# charging.net
KiCad netlist of a schematic drawn in EAGLE
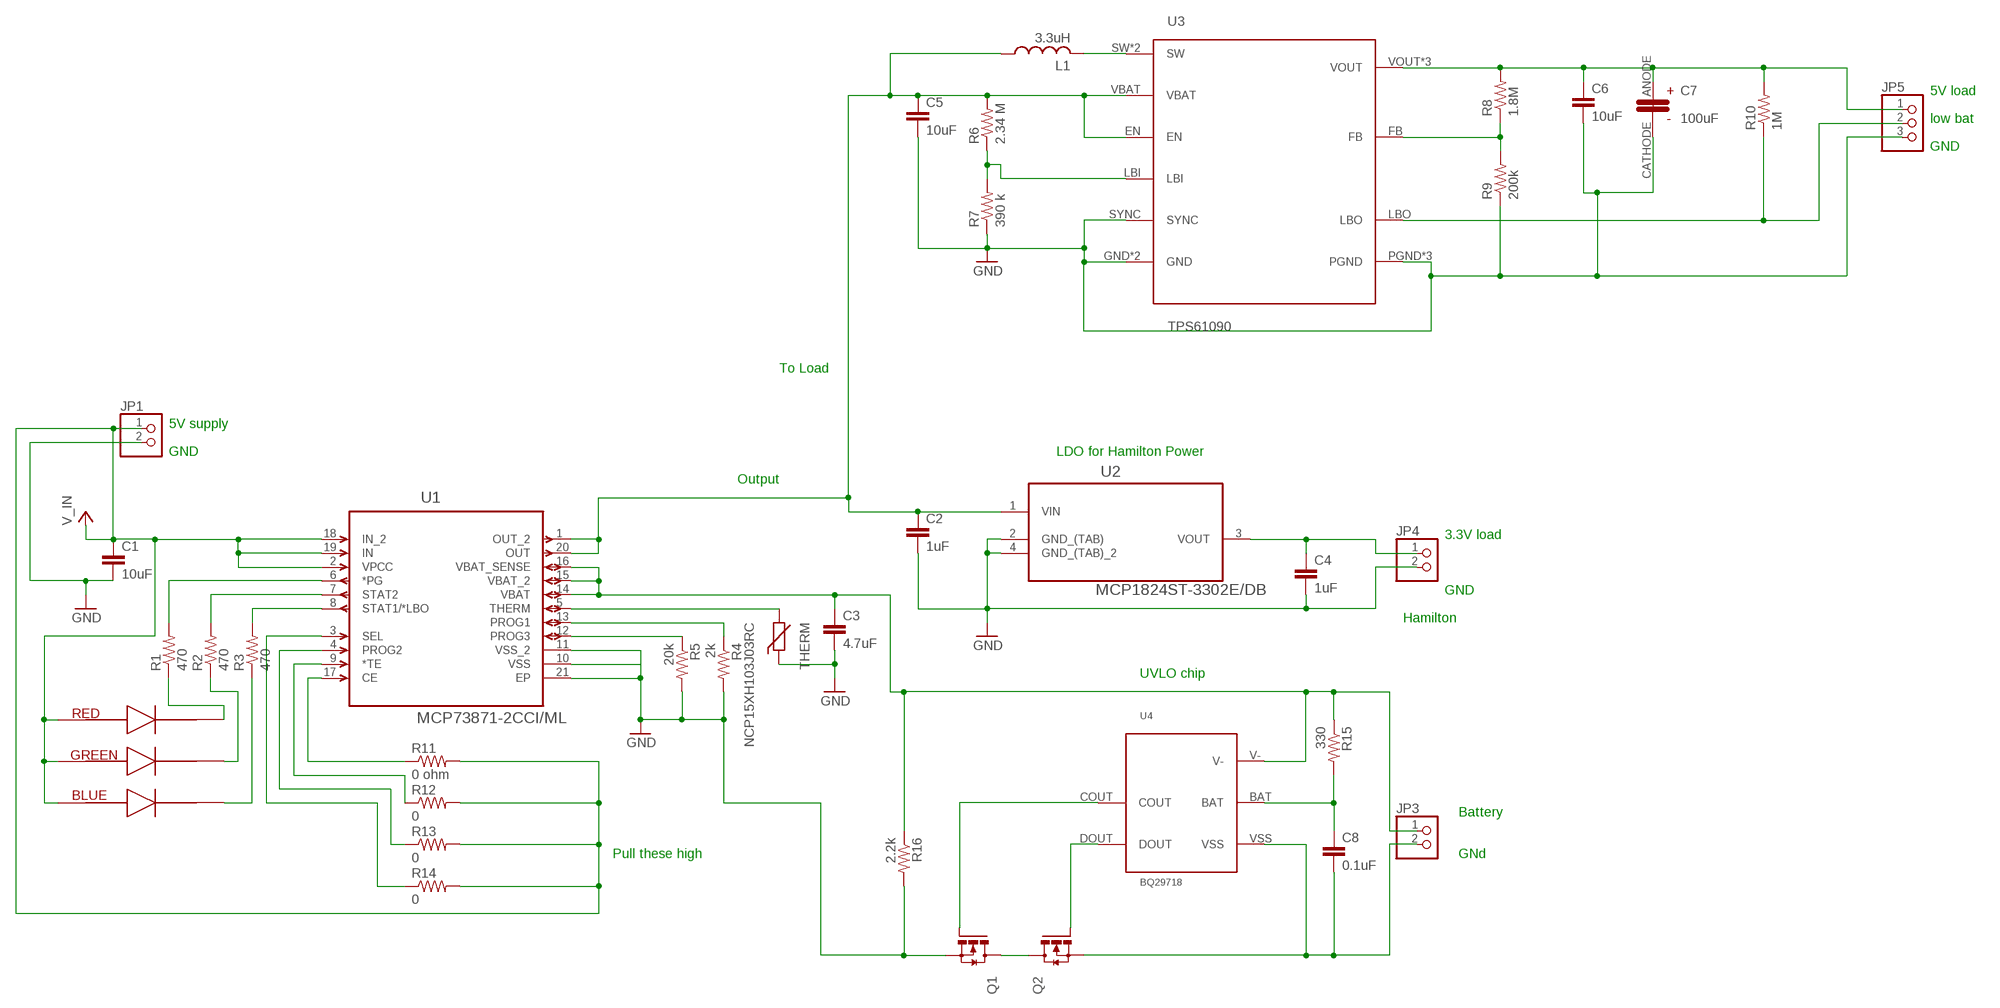
[diagram p0: schematic, sheet 1]

(export (version "E")
  (design (tool "Eeschema 10.0.6"))
  (components
    (comp (ref "C1")
      (value "10uF")
      (footprint "eagle-import:C0805")
      (libsource (lib "eagle-import") (part "C-EUC0805"))
    )
    (comp (ref "C2")
      (value "1uF")
      (footprint "eagle-import:C0603K")
      (libsource (lib "eagle-import") (part "C-EUC0603K"))
    )
    (comp (ref "C3")
      (value "4.7uF")
      (footprint "eagle-import:C0805")
      (libsource (lib "eagle-import") (part "C-EUC0805"))
    )
    (comp (ref "C4")
      (value "1uF")
      (footprint "eagle-import:C0603K")
      (libsource (lib "eagle-import") (part "C-EUC0603K"))
    )
    (comp (ref "C5")
      (value "10uF")
      (footprint "eagle-import:C0603K")
      (libsource (lib "eagle-import") (part "C-EUC0603K"))
    )
    (comp (ref "C6")
      (value "10uF")
      (footprint "eagle-import:C0603K")
      (libsource (lib "eagle-import") (part "C-EUC0603K"))
    )
    (comp (ref "C7")
      (value "100uF")
      (footprint "eagle-import:6032")
      (libsource (lib "eagle-import") (part "T491C686K010AT"))
    )
    (comp (ref "C8")
      (value "0.1uF")
      (footprint "eagle-import:C0805")
      (libsource (lib "eagle-import") (part "C-EUC0805"))
    )
    (comp (ref "JP1")
      (value "PINHD-1X2")
      (footprint "eagle-import:1X02")
      (libsource (lib "eagle-import") (part "PINHD-1X2"))
    )
    (comp (ref "JP3")
      (value "PINHD-1X2")
      (footprint "eagle-import:1X02")
      (libsource (lib "eagle-import") (part "PINHD-1X2"))
    )
    (comp (ref "JP4")
      (value "PINHD-1X2")
      (footprint "eagle-import:1X02")
      (libsource (lib "eagle-import") (part "PINHD-1X2"))
    )
    (comp (ref "JP5")
      (value "PINHD-1X3")
      (footprint "eagle-import:1X03")
      (libsource (lib "eagle-import") (part "PINHD-1X3"))
    )
    (comp (ref "L1")
      (value "3.3uH")
      (footprint "eagle-import:2-SMD")
      (libsource (lib "eagle-import") (part "L-US"))
    )
    (comp (ref "Q1")
      (value "CSD16301Q2")
      (footprint "eagle-import:6-SMD")
      (libsource (lib "eagle-import") (part "CSD16301Q2"))
    )
    (comp (ref "Q2")
      (value "CSD16301Q2")
      (footprint "eagle-import:6-SMD")
      (libsource (lib "eagle-import") (part "CSD16301Q2"))
    )
    (comp (ref "R1")
      (value "470")
      (footprint "eagle-import:R0805")
      (libsource (lib "eagle-import") (part "R-US_R0805"))
    )
    (comp (ref "R2")
      (value "470")
      (footprint "eagle-import:R0805")
      (libsource (lib "eagle-import") (part "R-US_R0805"))
    )
    (comp (ref "R3")
      (value "470")
      (footprint "eagle-import:R0805")
      (libsource (lib "eagle-import") (part "R-US_R0805"))
    )
    (comp (ref "R4")
      (value "2k")
      (footprint "eagle-import:R0805")
      (libsource (lib "eagle-import") (part "R-US_R0805"))
    )
    (comp (ref "R5")
      (value "20k")
      (footprint "eagle-import:R0805")
      (libsource (lib "eagle-import") (part "R-US_R0805"))
    )
    (comp (ref "R6")
      (value "2.34 M")
      (footprint "eagle-import:R0603")
      (libsource (lib "eagle-import") (part "R-US_R0603"))
    )
    (comp (ref "R7")
      (value "390 k")
      (footprint "eagle-import:R0603")
      (libsource (lib "eagle-import") (part "R-US_R0603"))
    )
    (comp (ref "R8")
      (value "1.8M")
      (footprint "eagle-import:R0603")
      (libsource (lib "eagle-import") (part "R-US_R0603"))
    )
    (comp (ref "R9")
      (value "200k")
      (footprint "eagle-import:R0603")
      (libsource (lib "eagle-import") (part "R-US_R0603"))
    )
    (comp (ref "R10")
      (value "1M")
      (footprint "eagle-import:R0603")
      (libsource (lib "eagle-import") (part "R-US_R0603"))
    )
    (comp (ref "R11")
      (value "0 ohm")
      (footprint "eagle-import:R0603")
      (libsource (lib "eagle-import") (part "R-US_R0603"))
    )
    (comp (ref "R12")
      (value "0")
      (footprint "eagle-import:R0603")
      (libsource (lib "eagle-import") (part "R-US_R0603"))
    )
    (comp (ref "R13")
      (value "0")
      (footprint "eagle-import:R0603")
      (libsource (lib "eagle-import") (part "R-US_R0603"))
    )
    (comp (ref "R14")
      (value "0")
      (footprint "eagle-import:R0603")
      (libsource (lib "eagle-import") (part "R-US_R0603"))
    )
    (comp (ref "R15")
      (value "330")
      (footprint "eagle-import:R0805")
      (libsource (lib "eagle-import") (part "R-US_R0805"))
    )
    (comp (ref "R16")
      (value "2.2k")
      (footprint "eagle-import:R0805")
      (libsource (lib "eagle-import") (part "R-US_R0805"))
    )
    (comp (ref "THERM")
      (value "NCP15XH103J03RC")
      (footprint "eagle-import:CT_CN0402")
      (libsource (lib "eagle-import") (part "NCP15XH103J03RC"))
    )
    (comp (ref "U$1")
      (value "CLP6C-FKB")
      (footprint "eagle-import:CREE_PLCC6_3-IN-1_SMD_LED_CLP6C-FKB")
      (libsource (lib "eagle-import") (part "CLP6C-FKB"))
    )
    (comp (ref "U1")
      (value "MCP73871-2CCI/ML")
      (footprint "eagle-import:QFN50P400X400X100-21N")
      (libsource (lib "eagle-import") (part "MCP73871-2CCI/ML"))
    )
    (comp (ref "U2")
      (value "MCP1824ST-3302E/DB")
      (footprint "eagle-import:SOT230P700X180-4N")
      (libsource (lib "eagle-import") (part "MCP1824ST-3302E/DB"))
    )
    (comp (ref "U3")
      (value "TPS61090")
      (footprint "eagle-import:QFN-16")
      (libsource (lib "eagle-import") (part "TPS61090"))
    )
    (comp (ref "U4")
      (value "BQ29718")
      (footprint "eagle-import:6-WFDFN")
      (libsource (lib "eagle-import") (part "BQ29718"))
    )
  )
  (nets
    (net (code "1") (name "GND") (class "Default")
      (node (ref "C1") (pin "2") (pinfunction "2_2") (pintype "passive"))
      (node (ref "C2") (pin "2") (pinfunction "2_2") (pintype "passive"))
      (node (ref "C3") (pin "2") (pinfunction "2_2") (pintype "passive"))
      (node (ref "C4") (pin "2") (pinfunction "2_2") (pintype "passive"))
      (node (ref "C5") (pin "2") (pinfunction "2_2") (pintype "passive"))
      (node (ref "C6") (pin "2") (pinfunction "2_2") (pintype "passive"))
      (node (ref "C7") (pin "CATHODE") (pinfunction "CATHODE_CATHODE") (pintype "bidirectional"))
      (node (ref "JP1") (pin "2") (pinfunction "2_2") (pintype "passive"))
      (node (ref "JP4") (pin "2") (pinfunction "2_2") (pintype "passive"))
      (node (ref "JP5") (pin "3") (pinfunction "3_3") (pintype "passive"))
      (node (ref "Q1") (pin "S_1") (pinfunction "S_S_1") (pintype "passive"))
      (node (ref "Q1") (pin "S_2") (pinfunction "S_S_2") (pintype "passive"))
      (node (ref "R16") (pin "2") (pinfunction "2_2") (pintype "passive"))
      (node (ref "R4") (pin "2") (pinfunction "2_2") (pintype "passive"))
      (node (ref "R5") (pin "2") (pinfunction "2_2") (pintype "passive"))
      (node (ref "R7") (pin "1") (pinfunction "1_1") (pintype "passive"))
      (node (ref "R9") (pin "1") (pinfunction "1_1") (pintype "passive"))
      (node (ref "THERM") (pin "1") (pinfunction "1_1") (pintype "passive"))
      (node (ref "U1") (pin "10") (pinfunction "VSS_10") (pintype "power_in"))
      (node (ref "U1") (pin "11") (pinfunction "VSS_2_11") (pintype "power_in"))
      (node (ref "U1") (pin "21") (pinfunction "EP_21") (pintype "passive"))
      (node (ref "U2") (pin "2") (pinfunction "GND_(TAB)_2") (pintype "passive"))
      (node (ref "U2") (pin "4") (pinfunction "GND_(TAB)_2_4") (pintype "passive"))
      (node (ref "U3") (pin "GND") (pinfunction "GND_GND") (pintype "bidirectional"))
      (node (ref "U3") (pin "P$17") (pinfunction "GND_P$17") (pintype "bidirectional"))
      (node (ref "U3") (pin "PGND") (pinfunction "PGND_PGND") (pintype "bidirectional"))
      (node (ref "U3") (pin "PGND_2") (pinfunction "PGND_PGND_2") (pintype "bidirectional"))
      (node (ref "U3") (pin "PGND_3") (pinfunction "PGND_PGND_3") (pintype "bidirectional"))
      (node (ref "U3") (pin "SYNC") (pinfunction "SYNC_SYNC") (pintype "bidirectional"))
    )
    (net (code "2") (name "Net-(C6-Pad1)") (class "Default")
      (node (ref "C6") (pin "1") (pinfunction "1_1") (pintype "passive"))
      (node (ref "C7") (pin "ANODE") (pinfunction "ANODE_ANODE") (pintype "bidirectional"))
      (node (ref "JP5") (pin "1") (pinfunction "1_1") (pintype "passive"))
      (node (ref "R10") (pin "2") (pinfunction "2_2") (pintype "passive"))
      (node (ref "R8") (pin "2") (pinfunction "2_2") (pintype "passive"))
      (node (ref "U3") (pin "VOUT") (pinfunction "VOUT_VOUT") (pintype "bidirectional"))
      (node (ref "U3") (pin "VOUT_2") (pinfunction "VOUT_VOUT_2") (pintype "bidirectional"))
      (node (ref "U3") (pin "VOUT_3") (pinfunction "VOUT_VOUT_3") (pintype "bidirectional"))
    )
    (net (code "3") (name "Net-(C8-Pad1)") (class "Default")
      (node (ref "C8") (pin "1") (pinfunction "1_1") (pintype "passive"))
      (node (ref "R15") (pin "2") (pinfunction "2_2") (pintype "passive"))
      (node (ref "U4") (pin "BAT") (pinfunction "BAT_BAT") (pintype "bidirectional"))
    )
    (net (code "4") (name "Net-(C8-Pad2)") (class "Default")
      (node (ref "C8") (pin "2") (pinfunction "2_2") (pintype "passive"))
      (node (ref "JP3") (pin "2") (pinfunction "2_2") (pintype "passive"))
      (node (ref "Q2") (pin "S_1") (pinfunction "S_S_1") (pintype "passive"))
      (node (ref "Q2") (pin "S_2") (pinfunction "S_S_2") (pintype "passive"))
      (node (ref "U4") (pin "VSS") (pinfunction "VSS_VSS") (pintype "bidirectional"))
    )
    (net (code "5") (name "Net-(JP5-Pad2)") (class "Default")
      (node (ref "JP5") (pin "2") (pinfunction "2_2") (pintype "passive"))
      (node (ref "R10") (pin "1") (pinfunction "1_1") (pintype "passive"))
      (node (ref "U3") (pin "LBO") (pinfunction "LBO_LBO") (pintype "bidirectional"))
    )
    (net (code "6") (name "Net-(L1-1)") (class "Default")
      (node (ref "C2") (pin "1") (pinfunction "1_1") (pintype "passive"))
      (node (ref "C5") (pin "1") (pinfunction "1_1") (pintype "passive"))
      (node (ref "L1") (pin "P$1") (pinfunction "1_P$1") (pintype "passive"))
      (node (ref "R6") (pin "2") (pinfunction "2_2") (pintype "passive"))
      (node (ref "U1") (pin "1") (pinfunction "OUT_2_1") (pintype "output"))
      (node (ref "U1") (pin "20") (pinfunction "OUT_20") (pintype "output"))
      (node (ref "U2") (pin "1") (pinfunction "VIN_1") (pintype "input"))
      (node (ref "U3") (pin "EN") (pinfunction "EN_EN") (pintype "bidirectional"))
      (node (ref "U3") (pin "VBAT") (pinfunction "VBAT_VBAT") (pintype "bidirectional"))
    )
    (net (code "7") (name "Net-(L1-2)") (class "Default")
      (node (ref "L1") (pin "P$2") (pinfunction "2_P$2") (pintype "passive"))
      (node (ref "U3") (pin "SW") (pinfunction "SW_SW") (pintype "bidirectional"))
      (node (ref "U3") (pin "SW_2") (pinfunction "SW_SW_2") (pintype "bidirectional"))
    )
    (net (code "8") (name "Net-(Q1-D-PadD_1)") (class "Default")
      (node (ref "Q1") (pin "D_1") (pinfunction "D_D_1") (pintype "passive"))
      (node (ref "Q1") (pin "D_2") (pinfunction "D_D_2") (pintype "passive"))
      (node (ref "Q1") (pin "D_3") (pinfunction "D_D_3") (pintype "passive"))
      (node (ref "Q1") (pin "D_4") (pinfunction "D_D_4") (pintype "passive"))
      (node (ref "Q1") (pin "D_5") (pinfunction "D_D_5") (pintype "passive"))
      (node (ref "Q2") (pin "D_1") (pinfunction "D_D_1") (pintype "passive"))
      (node (ref "Q2") (pin "D_2") (pinfunction "D_D_2") (pintype "passive"))
      (node (ref "Q2") (pin "D_3") (pinfunction "D_D_3") (pintype "passive"))
      (node (ref "Q2") (pin "D_4") (pinfunction "D_D_4") (pintype "passive"))
      (node (ref "Q2") (pin "D_5") (pinfunction "D_D_5") (pintype "passive"))
    )
    (net (code "9") (name "Net-(Q1-PadG)") (class "Default")
      (node (ref "Q1") (pin "G") (pinfunction "G_G") (pintype "passive"))
      (node (ref "U4") (pin "COUT") (pinfunction "COUT_COUT") (pintype "bidirectional"))
    )
    (net (code "10") (name "Net-(Q2-PadG)") (class "Default")
      (node (ref "Q2") (pin "G") (pinfunction "G_G") (pintype "passive"))
      (node (ref "U4") (pin "DOUT") (pinfunction "DOUT_DOUT") (pintype "bidirectional"))
    )
    (net (code "11") (name "Net-(R1-Pad1)") (class "Default")
      (node (ref "R1") (pin "1") (pinfunction "1_1") (pintype "passive"))
      (node (ref "U$1") (pin "RED_CATHODE") (pinfunction "RED_CATHODE_RED_CATHODE") (pintype "bidirectional"))
    )
    (net (code "12") (name "Net-(R2-Pad1)") (class "Default")
      (node (ref "R2") (pin "1") (pinfunction "1_1") (pintype "passive"))
      (node (ref "U$1") (pin "GREEN_CATHODE") (pinfunction "GREEN_CATHODE_GREEN_CATHODE") (pintype "bidirectional"))
    )
    (net (code "13") (name "Net-(R3-Pad1)") (class "Default")
      (node (ref "R3") (pin "1") (pinfunction "1_1") (pintype "passive"))
      (node (ref "U$1") (pin "BLUE_CATHODE") (pinfunction "BLUE_CATHODE_BLUE_CATHODE") (pintype "bidirectional"))
    )
    (net (code "14") (name "Net-(R6-Pad1)") (class "Default")
      (node (ref "R6") (pin "1") (pinfunction "1_1") (pintype "passive"))
      (node (ref "R7") (pin "2") (pinfunction "2_2") (pintype "passive"))
      (node (ref "U3") (pin "LBI") (pinfunction "LBI_LBI") (pintype "bidirectional"))
    )
    (net (code "15") (name "Net-(R8-Pad1)") (class "Default")
      (node (ref "R8") (pin "1") (pinfunction "1_1") (pintype "passive"))
      (node (ref "R9") (pin "2") (pinfunction "2_2") (pintype "passive"))
      (node (ref "U3") (pin "FB") (pinfunction "FB_FB") (pintype "bidirectional"))
    )
    (net (code "16") (name "Net-(U1-*PG)") (class "Default")
      (node (ref "R1") (pin "2") (pinfunction "2_2") (pintype "passive"))
      (node (ref "U1") (pin "6") (pinfunction "*PG_6") (pintype "output"))
    )
    (net (code "17") (name "Net-(U1-*TE)") (class "Default")
      (node (ref "R12") (pin "1") (pinfunction "1_1") (pintype "passive"))
      (node (ref "U1") (pin "9") (pinfunction "*TE_9") (pintype "input"))
    )
    (net (code "18") (name "Net-(U1-CE)") (class "Default")
      (node (ref "R11") (pin "1") (pinfunction "1_1") (pintype "passive"))
      (node (ref "U1") (pin "17") (pinfunction "CE_17") (pintype "input"))
    )
    (net (code "19") (name "Net-(U1-PROG1)") (class "Default")
      (node (ref "R4") (pin "1") (pinfunction "1_1") (pintype "passive"))
      (node (ref "U1") (pin "13") (pinfunction "PROG1_13") (pintype "bidirectional"))
    )
    (net (code "20") (name "Net-(U1-PROG2)") (class "Default")
      (node (ref "R13") (pin "1") (pinfunction "1_1") (pintype "passive"))
      (node (ref "U1") (pin "4") (pinfunction "PROG2_4") (pintype "input"))
    )
    (net (code "21") (name "Net-(U1-PROG3)") (class "Default")
      (node (ref "R5") (pin "1") (pinfunction "1_1") (pintype "passive"))
      (node (ref "U1") (pin "12") (pinfunction "PROG3_12") (pintype "bidirectional"))
    )
    (net (code "22") (name "Net-(U1-SEL)") (class "Default")
      (node (ref "R14") (pin "1") (pinfunction "1_1") (pintype "passive"))
      (node (ref "U1") (pin "3") (pinfunction "SEL_3") (pintype "input"))
    )
    (net (code "23") (name "Net-(U1-STAT1{slash}*LBO)") (class "Default")
      (node (ref "R3") (pin "2") (pinfunction "2_2") (pintype "passive"))
      (node (ref "U1") (pin "8") (pinfunction "STAT1/*LBO_8") (pintype "output"))
    )
    (net (code "24") (name "Net-(U1-STAT2)") (class "Default")
      (node (ref "R2") (pin "2") (pinfunction "2_2") (pintype "passive"))
      (node (ref "U1") (pin "7") (pinfunction "STAT2_7") (pintype "output"))
    )
    (net (code "25") (name "Net-(U1-THERM)") (class "Default")
      (node (ref "THERM") (pin "2") (pinfunction "2_2") (pintype "passive"))
      (node (ref "U1") (pin "5") (pinfunction "THERM_5") (pintype "bidirectional"))
    )
    (net (code "26") (name "Net-(U1-VBAT)") (class "Default")
      (node (ref "C3") (pin "1") (pinfunction "1_1") (pintype "passive"))
      (node (ref "JP3") (pin "1") (pinfunction "1_1") (pintype "passive"))
      (node (ref "R15") (pin "1") (pinfunction "1_1") (pintype "passive"))
      (node (ref "R16") (pin "1") (pinfunction "1_1") (pintype "passive"))
      (node (ref "U1") (pin "14") (pinfunction "VBAT_14") (pintype "bidirectional"))
      (node (ref "U1") (pin "15") (pinfunction "VBAT_2_15") (pintype "bidirectional"))
      (node (ref "U1") (pin "16") (pinfunction "VBAT_SENSE_16") (pintype "bidirectional"))
      (node (ref "U4") (pin "V-") (pinfunction "V-_V-") (pintype "bidirectional"))
    )
    (net (code "27") (name "Net-(U2-VOUT)") (class "Default")
      (node (ref "C4") (pin "1") (pinfunction "1_1") (pintype "passive"))
      (node (ref "JP4") (pin "1") (pinfunction "1_1") (pintype "passive"))
      (node (ref "U2") (pin "3") (pinfunction "VOUT_3") (pintype "output"))
    )
    (net (code "28") (name "V_IN") (class "Default")
      (node (ref "C1") (pin "1") (pinfunction "1_1") (pintype "passive"))
      (node (ref "JP1") (pin "1") (pinfunction "1_1") (pintype "passive"))
      (node (ref "R11") (pin "2") (pinfunction "2_2") (pintype "passive"))
      (node (ref "R12") (pin "2") (pinfunction "2_2") (pintype "passive"))
      (node (ref "R13") (pin "2") (pinfunction "2_2") (pintype "passive"))
      (node (ref "R14") (pin "2") (pinfunction "2_2") (pintype "passive"))
      (node (ref "U$1") (pin "BLUE_ANODE") (pinfunction "BLUE_ANODE_BLUE_ANODE") (pintype "bidirectional"))
      (node (ref "U$1") (pin "GREEN_ANODE") (pinfunction "GREEN_ANODE_GREEN_ANODE") (pintype "bidirectional"))
      (node (ref "U$1") (pin "RED_ANODE") (pinfunction "RED_ANODE_RED_ANODE") (pintype "bidirectional"))
      (node (ref "U1") (pin "18") (pinfunction "IN_2_18") (pintype "input"))
      (node (ref "U1") (pin "19") (pinfunction "IN_19") (pintype "input"))
      (node (ref "U1") (pin "2") (pinfunction "VPCC_2") (pintype "input"))
    )
  )
)
